# connector.net
KiCad netlist of a schematic drawn in EAGLE
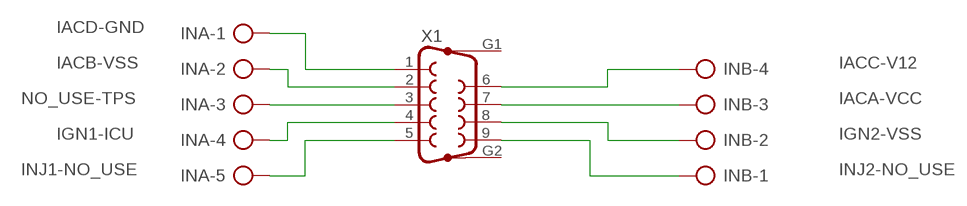
[diagram p0: schematic, sheet 1]

(export (version "E")
  (design (tool "Eeschema 10.0.6"))
  (components
    (comp (ref "INA")
      (value "AK500/5")
      (footprint "eagle-import:AK500_5")
      (libsource (lib "eagle-import") (part "AK500/5"))
    )
    (comp (ref "INB")
      (value "AK500/4")
      (footprint "eagle-import:AK500_4")
      (libsource (lib "eagle-import") (part "AK500/4"))
    )
    (comp (ref "X1")
      (value "F09HP")
      (footprint "eagle-import:F09HP")
      (libsource (lib "eagle-import") (part "F09HP"))
    )
  )
  (nets
    (net (code "1") (name "/IACA-VCC") (class "Default")
      (node (ref "INB") (pin "3") (pinfunction "KL_3") (pintype "passive"))
      (node (ref "X1") (pin "7") (pinfunction "7_7") (pintype "passive"))
    )
    (net (code "2") (name "/IACB-VSS") (class "Default")
      (node (ref "INA") (pin "2") (pinfunction "KL_2") (pintype "passive"))
      (node (ref "X1") (pin "2") (pinfunction "2_2") (pintype "passive"))
    )
    (net (code "3") (name "/IACC-V12") (class "Default")
      (node (ref "INB") (pin "4") (pinfunction "KL_4") (pintype "passive"))
      (node (ref "X1") (pin "6") (pinfunction "6_6") (pintype "passive"))
    )
    (net (code "4") (name "/IACD-GND") (class "Default")
      (node (ref "INA") (pin "1") (pinfunction "KL_1") (pintype "passive"))
      (node (ref "X1") (pin "1") (pinfunction "1_1") (pintype "passive"))
    )
    (net (code "5") (name "/IGN1-ICU") (class "Default")
      (node (ref "INA") (pin "4") (pinfunction "KL_4") (pintype "passive"))
      (node (ref "X1") (pin "4") (pinfunction "4_4") (pintype "passive"))
    )
    (net (code "6") (name "/IGN2-VSS") (class "Default")
      (node (ref "INB") (pin "2") (pinfunction "KL_2") (pintype "passive"))
      (node (ref "X1") (pin "8") (pinfunction "8_8") (pintype "passive"))
    )
    (net (code "7") (name "/INJ1-NO_USE") (class "Default")
      (node (ref "INA") (pin "5") (pinfunction "KL_5") (pintype "passive"))
      (node (ref "X1") (pin "5") (pinfunction "5_5") (pintype "passive"))
    )
    (net (code "8") (name "/INJ2-NO_USE") (class "Default")
      (node (ref "INB") (pin "1") (pinfunction "KL_1") (pintype "passive"))
      (node (ref "X1") (pin "9") (pinfunction "9_9") (pintype "passive"))
    )
    (net (code "9") (name "/NO_USE-TPS") (class "Default")
      (node (ref "INA") (pin "3") (pinfunction "KL_3") (pintype "passive"))
      (node (ref "X1") (pin "3") (pinfunction "3_3") (pintype "passive"))
    )
    (net (code "10") (name "unconnected-(X1-PadG1)") (class "Default")
      (node (ref "X1") (pin "G1") (pinfunction "G1_G1") (pintype "passive"))
    )
    (net (code "11") (name "unconnected-(X1-PadG2)") (class "Default")
      (node (ref "X1") (pin "G2") (pinfunction "G2_G2") (pintype "passive"))
    )
  )
)
